# Power.net
KiCad netlist of a schematic drawn in Altium Designer
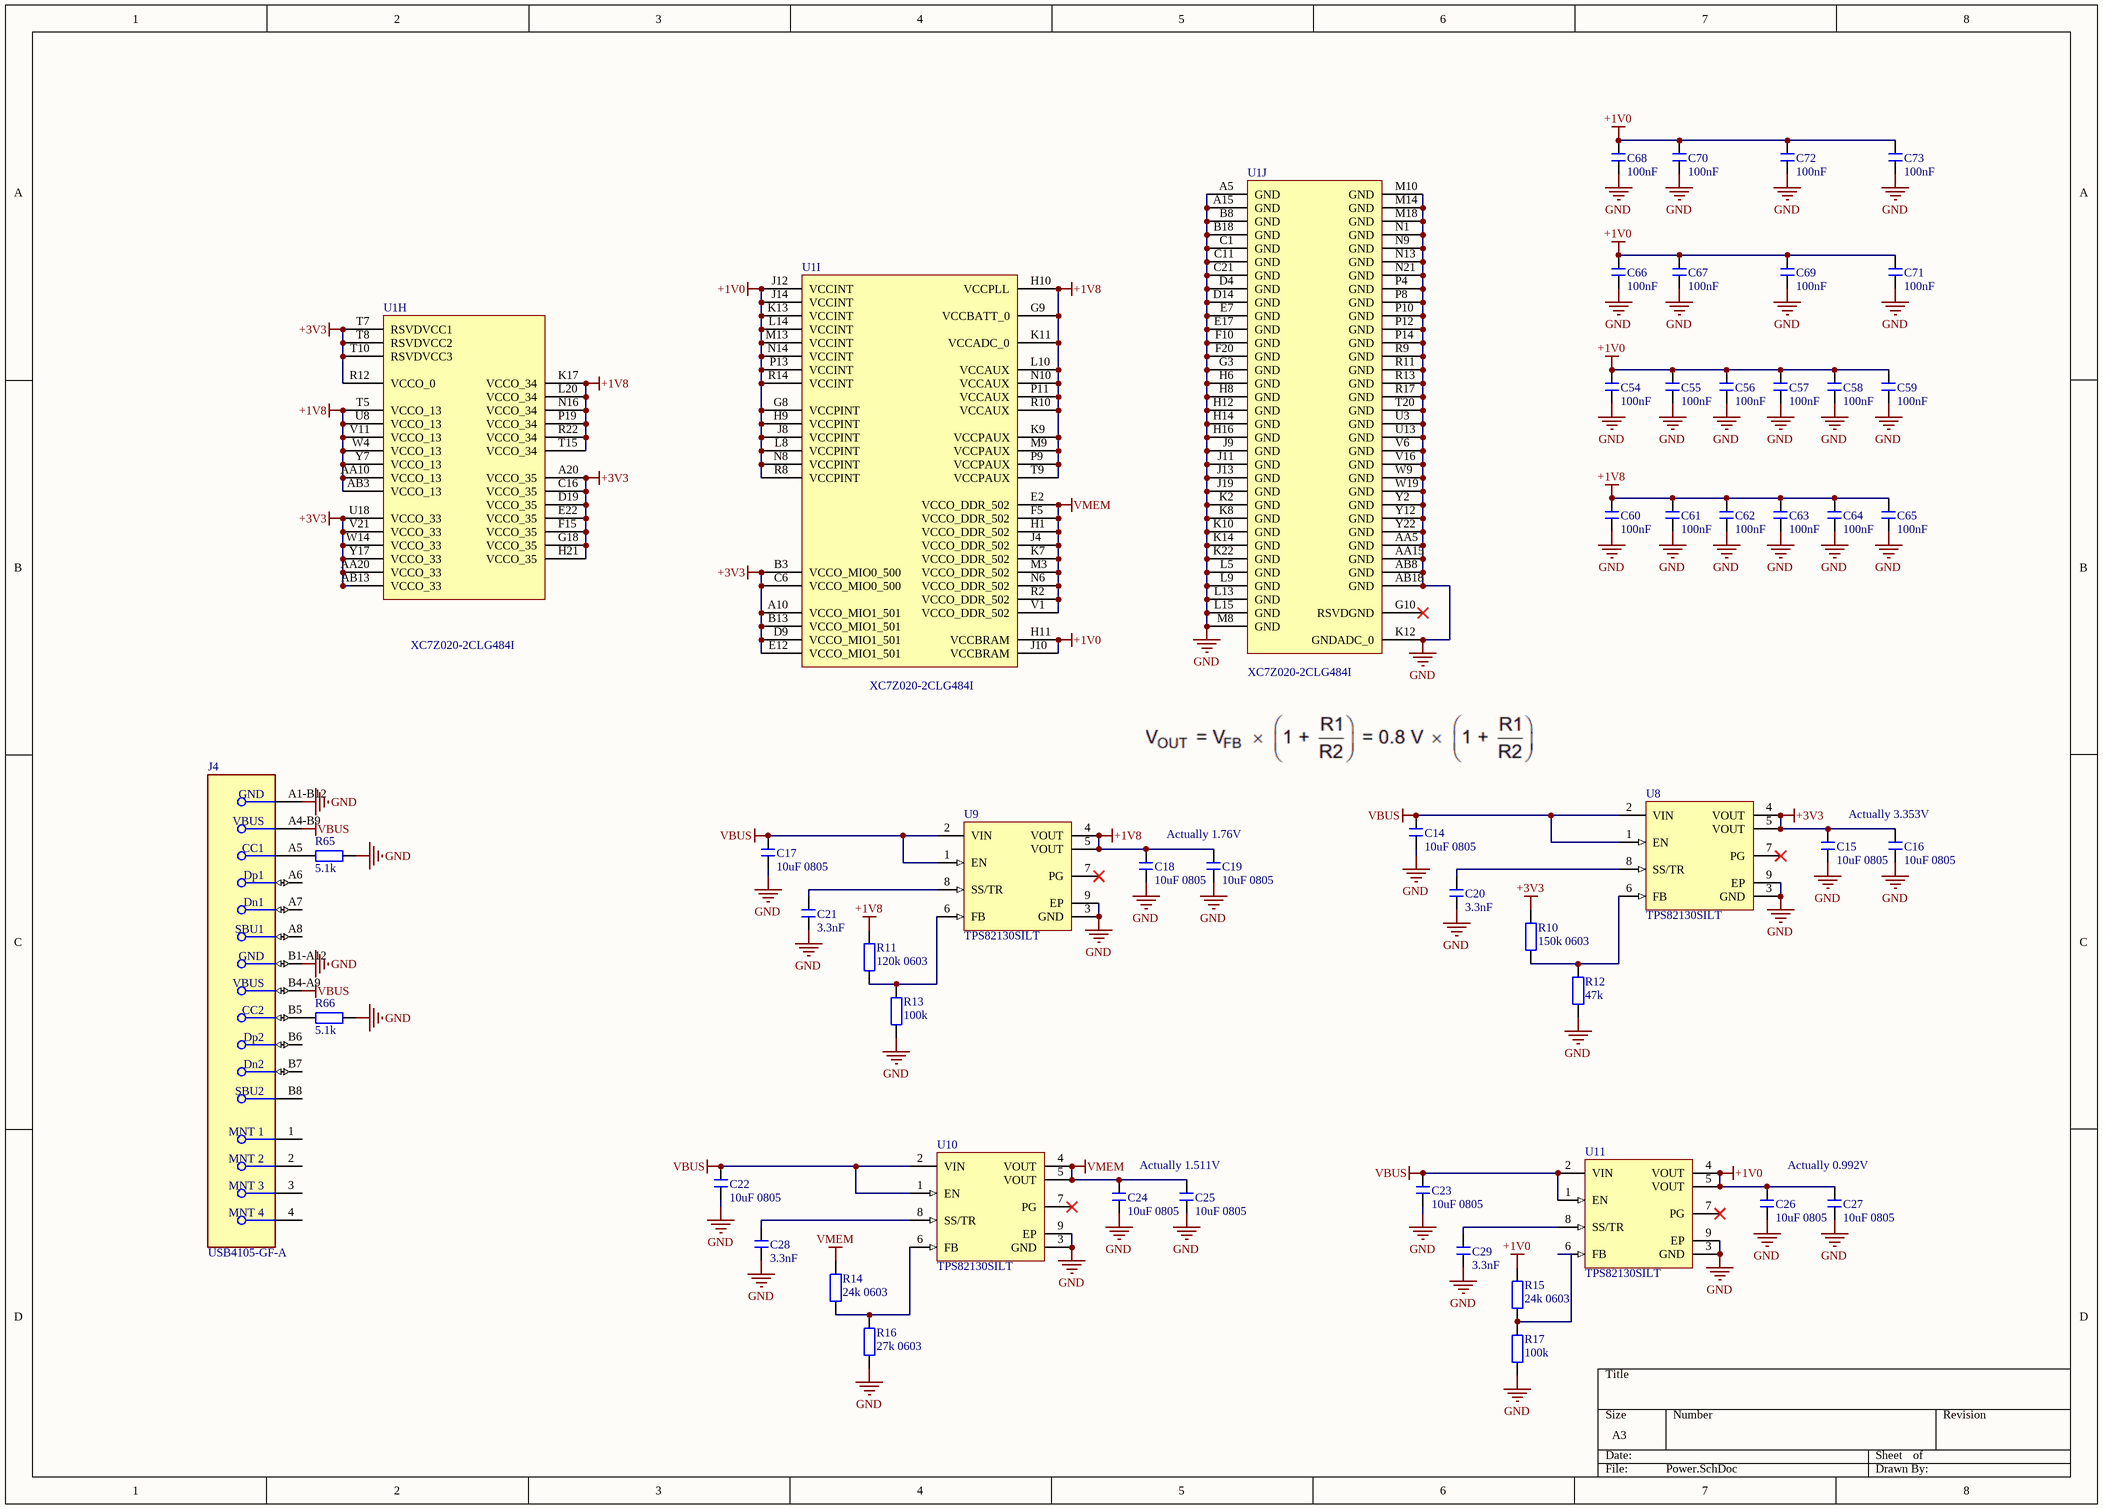
[diagram p0: Power.SchDoc]

(export (version "E")
  (design (tool "Eeschema 10.0.6"))
  (components
    (comp (ref "C14") (value "10uF 0805") (footprint "C0603") (libsource (lib "Passive") (part "C")))
    (comp (ref "C15") (value "10uF 0805") (footprint "C0603") (libsource (lib "Passive") (part "C")))
    (comp (ref "C16") (value "10uF 0805") (footprint "C0603") (libsource (lib "Passive") (part "C")))
    (comp (ref "C17") (value "10uF 0805") (footprint "C0603") (libsource (lib "Passive") (part "C")))
    (comp (ref "C18") (value "10uF 0805") (footprint "C0603") (libsource (lib "Passive") (part "C")))
    (comp (ref "C19") (value "10uF 0805") (footprint "C0603") (libsource (lib "Passive") (part "C")))
    (comp (ref "C20") (value "3.3nF") (footprint "C0402") (libsource (lib "Passive") (part "C")))
    (comp (ref "C21") (value "3.3nF") (footprint "C0402") (libsource (lib "Passive") (part "C")))
    (comp (ref "C22") (value "10uF 0805") (footprint "C0603") (libsource (lib "Passive") (part "C")))
    (comp (ref "C23") (value "10uF 0805") (footprint "C0603") (libsource (lib "Passive") (part "C")))
    (comp (ref "C24") (value "10uF 0805") (footprint "C0603") (libsource (lib "Passive") (part "C")))
    (comp (ref "C25") (value "10uF 0805") (footprint "C0603") (libsource (lib "Passive") (part "C")))
    (comp (ref "C26") (value "10uF 0805") (footprint "C0603") (libsource (lib "Passive") (part "C")))
    (comp (ref "C27") (value "10uF 0805") (footprint "C0603") (libsource (lib "Passive") (part "C")))
    (comp (ref "C28") (value "3.3nF") (footprint "C0402") (libsource (lib "Passive") (part "C")))
    (comp (ref "C29") (value "3.3nF") (footprint "C0402") (libsource (lib "Passive") (part "C")))
    (comp (ref "C54") (value "100nF") (footprint "C0402") (libsource (lib "Passive") (part "C")))
    (comp (ref "C55") (value "100nF") (footprint "C0402") (libsource (lib "Passive") (part "C")))
    (comp (ref "C56") (value "100nF") (footprint "C0402") (libsource (lib "Passive") (part "C")))
    (comp (ref "C57") (value "100nF") (footprint "C0402") (libsource (lib "Passive") (part "C")))
    (comp (ref "C58") (value "100nF") (footprint "C0402") (libsource (lib "Passive") (part "C")))
    (comp (ref "C59") (value "100nF") (footprint "C0402") (libsource (lib "Passive") (part "C")))
    (comp (ref "C60") (value "100nF") (footprint "C0402") (libsource (lib "Passive") (part "C")))
    (comp (ref "C61") (value "100nF") (footprint "C0402") (libsource (lib "Passive") (part "C")))
    (comp (ref "C62") (value "100nF") (footprint "C0402") (libsource (lib "Passive") (part "C")))
    (comp (ref "C63") (value "100nF") (footprint "C0402") (libsource (lib "Passive") (part "C")))
    (comp (ref "C64") (value "100nF") (footprint "C0402") (libsource (lib "Passive") (part "C")))
    (comp (ref "C65") (value "100nF") (footprint "C0402") (libsource (lib "Passive") (part "C")))
    (comp (ref "C66") (value "100nF") (footprint "C0402") (libsource (lib "Passive") (part "C")))
    (comp (ref "C67") (value "100nF") (footprint "C0402") (libsource (lib "Passive") (part "C")))
    (comp (ref "C68") (value "100nF") (footprint "C0402") (libsource (lib "Passive") (part "C")))
    (comp (ref "C69") (value "100nF") (footprint "C0402") (libsource (lib "Passive") (part "C")))
    (comp (ref "C70") (value "100nF") (footprint "C0402") (libsource (lib "Passive") (part "C")))
    (comp (ref "C71") (value "100nF") (footprint "C0402") (libsource (lib "Passive") (part "C")))
    (comp (ref "C72") (value "100nF") (footprint "C0402") (libsource (lib "Passive") (part "C")))
    (comp (ref "C73") (value "100nF") (footprint "C0402") (libsource (lib "Passive") (part "C")))
    (comp (ref "J4")
      (value "USB4105-GF-A")
      (footprint "FP-USB4105-GF-A-MFG")
      (description "CONN RCPT USB2.0 TYPEC 5A")
      (fields
        (field (name "MANUFACTURER") "GCT")
        (field (name "OCTOPART") "https://octopart.com/usb4105-gf-a-gct-106627878")
      )
      (libsource (lib "Altium Content Vault") (part "e7c17a616881a82b79941196b4bec10"))
    )
    (comp (ref "R10") (value "150k 0603") (footprint "R0603") (libsource (lib "Passive") (part "R")))
    (comp (ref "R11") (value "120k 0603") (footprint "R0603") (libsource (lib "Passive") (part "R")))
    (comp (ref "R12") (value "47k") (footprint "R0402") (libsource (lib "Passive") (part "R")))
    (comp (ref "R13") (value "100k") (footprint "R0402") (libsource (lib "Passive") (part "R")))
    (comp (ref "R14") (value "24k 0603") (footprint "R0603") (libsource (lib "Passive") (part "R")))
    (comp (ref "R15") (value "24k 0603") (footprint "R0603") (libsource (lib "Passive") (part "R")))
    (comp (ref "R16") (value "27k 0603") (footprint "R0603") (libsource (lib "Passive") (part "R")))
    (comp (ref "R17") (value "100k") (footprint "R0402") (libsource (lib "Passive") (part "R")))
    (comp (ref "R65") (value "5.1k") (footprint "R0402") (libsource (lib "Passive") (part "R")))
    (comp (ref "R66") (value "5.1k") (footprint "R0402") (libsource (lib "Passive") (part "R")))
    (comp (ref "U1")
      (value "XC7Z020-2CLG484I")
      (footprint "CLG484")
      (fields (field (name "GENERIC PART NUMBER") "XC7Z020"))
      (libsource (lib "Altium Content Vault") (part "XNLX-XC7Z020-CLG484"))
    )
    (comp (ref "U8")
      (value "TPS82130SILT")
      (footprint "SIL0008D_V")
      (fields (field (name "MANUFACTURER") "Texas Instruments"))
      (libsource (lib "Altium Content Vault") (part "TI-TPS82130-SIL-8"))
    )
    (comp (ref "U9")
      (value "TPS82130SILT")
      (footprint "SIL0008D_V")
      (fields (field (name "MANUFACTURER") "Texas Instruments"))
      (libsource (lib "Altium Content Vault") (part "TI-TPS82130-SIL-8"))
    )
    (comp (ref "U10")
      (value "TPS82130SILT")
      (footprint "SIL0008D_V")
      (fields (field (name "MANUFACTURER") "Texas Instruments"))
      (libsource (lib "Altium Content Vault") (part "TI-TPS82130-SIL-8"))
    )
    (comp (ref "U11")
      (value "TPS82130SILT")
      (footprint "SIL0008D_V")
      (fields (field (name "MANUFACTURER") "Texas Instruments"))
      (libsource (lib "Altium Content Vault") (part "TI-TPS82130-SIL-8"))
    )
  )
  (nets
    (net (code "1") (name "+1V0") (class "Default")
      (node (ref "C26") (pin "2") (pinfunction "2_2") (pintype "passive"))
      (node (ref "C27") (pin "2") (pinfunction "2_2") (pintype "passive"))
      (node (ref "C54") (pin "2") (pinfunction "2_2") (pintype "passive"))
      (node (ref "C55") (pin "2") (pinfunction "2_2") (pintype "passive"))
      (node (ref "C56") (pin "2") (pinfunction "2_2") (pintype "passive"))
      (node (ref "C57") (pin "2") (pinfunction "2_2") (pintype "passive"))
      (node (ref "C58") (pin "2") (pinfunction "2_2") (pintype "passive"))
      (node (ref "C59") (pin "2") (pinfunction "2_2") (pintype "passive"))
      (node (ref "C66") (pin "2") (pinfunction "2_2") (pintype "passive"))
      (node (ref "C67") (pin "2") (pinfunction "2_2") (pintype "passive"))
      (node (ref "C68") (pin "2") (pinfunction "2_2") (pintype "passive"))
      (node (ref "C69") (pin "2") (pinfunction "2_2") (pintype "passive"))
      (node (ref "C70") (pin "2") (pinfunction "2_2") (pintype "passive"))
      (node (ref "C71") (pin "2") (pinfunction "2_2") (pintype "passive"))
      (node (ref "C72") (pin "2") (pinfunction "2_2") (pintype "passive"))
      (node (ref "C73") (pin "2") (pinfunction "2_2") (pintype "passive"))
      (node (ref "R15") (pin "1") (pinfunction "1_1") (pintype "passive"))
      (node (ref "U1") (pin "G8") (pinfunction "VCCPINT_G8") (pintype "power_in"))
      (node (ref "U1") (pin "H11") (pinfunction "VCCBRAM_H11") (pintype "power_in"))
      (node (ref "U1") (pin "H9") (pinfunction "VCCPINT_H9") (pintype "power_in"))
      (node (ref "U1") (pin "J10") (pinfunction "VCCBRAM_J10") (pintype "power_in"))
      (node (ref "U1") (pin "J12") (pinfunction "VCCINT_J12") (pintype "power_in"))
      (node (ref "U1") (pin "J14") (pinfunction "VCCINT_J14") (pintype "power_in"))
      (node (ref "U1") (pin "J8") (pinfunction "VCCPINT_J8") (pintype "power_in"))
      (node (ref "U1") (pin "K13") (pinfunction "VCCINT_K13") (pintype "power_in"))
      (node (ref "U1") (pin "L14") (pinfunction "VCCINT_L14") (pintype "power_in"))
      (node (ref "U1") (pin "L8") (pinfunction "VCCPINT_L8") (pintype "power_in"))
      (node (ref "U1") (pin "M13") (pinfunction "VCCINT_M13") (pintype "power_in"))
      (node (ref "U1") (pin "N14") (pinfunction "VCCINT_N14") (pintype "power_in"))
      (node (ref "U1") (pin "N8") (pinfunction "VCCPINT_N8") (pintype "power_in"))
      (node (ref "U1") (pin "P13") (pinfunction "VCCINT_P13") (pintype "power_in"))
      (node (ref "U1") (pin "R14") (pinfunction "VCCINT_R14") (pintype "power_in"))
      (node (ref "U1") (pin "R8") (pinfunction "VCCPINT_R8") (pintype "power_in"))
      (node (ref "U11") (pin "4") (pinfunction "VOUT_4") (pintype "power_in"))
      (node (ref "U11") (pin "5") (pinfunction "VOUT_5") (pintype "power_in"))
    )
    (net (code "2") (name "+1V8") (class "Default")
      (node (ref "C18") (pin "2") (pinfunction "2_2") (pintype "passive"))
      (node (ref "C19") (pin "2") (pinfunction "2_2") (pintype "passive"))
      (node (ref "C60") (pin "2") (pinfunction "2_2") (pintype "passive"))
      (node (ref "C61") (pin "2") (pinfunction "2_2") (pintype "passive"))
      (node (ref "C62") (pin "2") (pinfunction "2_2") (pintype "passive"))
      (node (ref "C63") (pin "2") (pinfunction "2_2") (pintype "passive"))
      (node (ref "C64") (pin "2") (pinfunction "2_2") (pintype "passive"))
      (node (ref "C65") (pin "2") (pinfunction "2_2") (pintype "passive"))
      (node (ref "R11") (pin "1") (pinfunction "1_1") (pintype "passive"))
      (node (ref "U1") (pin "AA10") (pinfunction "VCCO_13_AA10") (pintype "power_in"))
      (node (ref "U1") (pin "AB3") (pinfunction "VCCO_13_AB3") (pintype "power_in"))
      (node (ref "U1") (pin "G9") (pinfunction "VCCBATT_0_G9") (pintype "power_in"))
      (node (ref "U1") (pin "H10") (pinfunction "VCCPLL_H10") (pintype "power_in"))
      (node (ref "U1") (pin "K11") (pinfunction "VCCADC_0_K11") (pintype "power_in"))
      (node (ref "U1") (pin "K17") (pinfunction "VCCO_34_K17") (pintype "power_in"))
      (node (ref "U1") (pin "K9") (pinfunction "VCCPAUX_K9") (pintype "power_in"))
      (node (ref "U1") (pin "L10") (pinfunction "VCCAUX_L10") (pintype "power_in"))
      (node (ref "U1") (pin "L20") (pinfunction "VCCO_34_L20") (pintype "power_in"))
      (node (ref "U1") (pin "M9") (pinfunction "VCCPAUX_M9") (pintype "power_in"))
      (node (ref "U1") (pin "N10") (pinfunction "VCCAUX_N10") (pintype "power_in"))
      (node (ref "U1") (pin "N16") (pinfunction "VCCO_34_N16") (pintype "power_in"))
      (node (ref "U1") (pin "P11") (pinfunction "VCCAUX_P11") (pintype "power_in"))
      (node (ref "U1") (pin "P19") (pinfunction "VCCO_34_P19") (pintype "power_in"))
      (node (ref "U1") (pin "P9") (pinfunction "VCCPAUX_P9") (pintype "power_in"))
      (node (ref "U1") (pin "R10") (pinfunction "VCCAUX_R10") (pintype "power_in"))
      (node (ref "U1") (pin "R22") (pinfunction "VCCO_34_R22") (pintype "power_in"))
      (node (ref "U1") (pin "T15") (pinfunction "VCCO_34_T15") (pintype "power_in"))
      (node (ref "U1") (pin "T5") (pinfunction "VCCO_13_T5") (pintype "power_in"))
      (node (ref "U1") (pin "T9") (pinfunction "VCCPAUX_T9") (pintype "power_in"))
      (node (ref "U1") (pin "U8") (pinfunction "VCCO_13_U8") (pintype "power_in"))
      (node (ref "U1") (pin "V11") (pinfunction "VCCO_13_V11") (pintype "power_in"))
      (node (ref "U1") (pin "W4") (pinfunction "VCCO_13_W4") (pintype "power_in"))
      (node (ref "U1") (pin "Y7") (pinfunction "VCCO_13_Y7") (pintype "power_in"))
      (node (ref "U9") (pin "4") (pinfunction "VOUT_4") (pintype "power_in"))
      (node (ref "U9") (pin "5") (pinfunction "VOUT_5") (pintype "power_in"))
    )
    (net (code "3") (name "+3V3") (class "Default")
      (node (ref "C15") (pin "2") (pinfunction "2_2") (pintype "passive"))
      (node (ref "C16") (pin "2") (pinfunction "2_2") (pintype "passive"))
      (node (ref "R10") (pin "1") (pinfunction "1_1") (pintype "passive"))
      (node (ref "U1") (pin "A10") (pinfunction "VCCO_MIO1_501_A10") (pintype "power_in"))
      (node (ref "U1") (pin "A20") (pinfunction "VCCO_35_A20") (pintype "power_in"))
      (node (ref "U1") (pin "AA20") (pinfunction "VCCO_33_AA20") (pintype "power_in"))
      (node (ref "U1") (pin "AB13") (pinfunction "VCCO_33_AB13") (pintype "power_in"))
      (node (ref "U1") (pin "B13") (pinfunction "VCCO_MIO1_501_B13") (pintype "power_in"))
      (node (ref "U1") (pin "B3") (pinfunction "VCCO_MIO0_500_B3") (pintype "power_in"))
      (node (ref "U1") (pin "C16") (pinfunction "VCCO_35_C16") (pintype "power_in"))
      (node (ref "U1") (pin "C6") (pinfunction "VCCO_MIO0_500_C6") (pintype "power_in"))
      (node (ref "U1") (pin "D19") (pinfunction "VCCO_35_D19") (pintype "power_in"))
      (node (ref "U1") (pin "D9") (pinfunction "VCCO_MIO1_501_D9") (pintype "power_in"))
      (node (ref "U1") (pin "E12") (pinfunction "VCCO_MIO1_501_E12") (pintype "power_in"))
      (node (ref "U1") (pin "E22") (pinfunction "VCCO_35_E22") (pintype "power_in"))
      (node (ref "U1") (pin "F15") (pinfunction "VCCO_35_F15") (pintype "power_in"))
      (node (ref "U1") (pin "G18") (pinfunction "VCCO_35_G18") (pintype "power_in"))
      (node (ref "U1") (pin "H21") (pinfunction "VCCO_35_H21") (pintype "power_in"))
      (node (ref "U1") (pin "R12") (pinfunction "VCCO_0_R12") (pintype "power_in"))
      (node (ref "U1") (pin "T10") (pinfunction "RSVDVCC3_T10") (pintype "power_in"))
      (node (ref "U1") (pin "T7") (pinfunction "RSVDVCC1_T7") (pintype "power_in"))
      (node (ref "U1") (pin "T8") (pinfunction "RSVDVCC2_T8") (pintype "power_in"))
      (node (ref "U1") (pin "U18") (pinfunction "VCCO_33_U18") (pintype "power_in"))
      (node (ref "U1") (pin "V21") (pinfunction "VCCO_33_V21") (pintype "power_in"))
      (node (ref "U1") (pin "W14") (pinfunction "VCCO_33_W14") (pintype "power_in"))
      (node (ref "U1") (pin "Y17") (pinfunction "VCCO_33_Y17") (pintype "power_in"))
      (node (ref "U8") (pin "4") (pinfunction "VOUT_4") (pintype "power_in"))
      (node (ref "U8") (pin "5") (pinfunction "VOUT_5") (pintype "power_in"))
    )
    (net (code "4") (name "GND") (class "Default")
      (node (ref "C14") (pin "1") (pinfunction "1_1") (pintype "passive"))
      (node (ref "C15") (pin "1") (pinfunction "1_1") (pintype "passive"))
      (node (ref "C16") (pin "1") (pinfunction "1_1") (pintype "passive"))
      (node (ref "C17") (pin "1") (pinfunction "1_1") (pintype "passive"))
      (node (ref "C18") (pin "1") (pinfunction "1_1") (pintype "passive"))
      (node (ref "C19") (pin "1") (pinfunction "1_1") (pintype "passive"))
      (node (ref "C20") (pin "1") (pinfunction "1_1") (pintype "passive"))
      (node (ref "C21") (pin "1") (pinfunction "1_1") (pintype "passive"))
      (node (ref "C22") (pin "1") (pinfunction "1_1") (pintype "passive"))
      (node (ref "C23") (pin "1") (pinfunction "1_1") (pintype "passive"))
      (node (ref "C24") (pin "1") (pinfunction "1_1") (pintype "passive"))
      (node (ref "C25") (pin "1") (pinfunction "1_1") (pintype "passive"))
      (node (ref "C26") (pin "1") (pinfunction "1_1") (pintype "passive"))
      (node (ref "C27") (pin "1") (pinfunction "1_1") (pintype "passive"))
      (node (ref "C28") (pin "1") (pinfunction "1_1") (pintype "passive"))
      (node (ref "C29") (pin "1") (pinfunction "1_1") (pintype "passive"))
      (node (ref "C54") (pin "1") (pinfunction "1_1") (pintype "passive"))
      (node (ref "C55") (pin "1") (pinfunction "1_1") (pintype "passive"))
      (node (ref "C56") (pin "1") (pinfunction "1_1") (pintype "passive"))
      (node (ref "C57") (pin "1") (pinfunction "1_1") (pintype "passive"))
      (node (ref "C58") (pin "1") (pinfunction "1_1") (pintype "passive"))
      (node (ref "C59") (pin "1") (pinfunction "1_1") (pintype "passive"))
      (node (ref "C60") (pin "1") (pinfunction "1_1") (pintype "passive"))
      (node (ref "C61") (pin "1") (pinfunction "1_1") (pintype "passive"))
      (node (ref "C62") (pin "1") (pinfunction "1_1") (pintype "passive"))
      (node (ref "C63") (pin "1") (pinfunction "1_1") (pintype "passive"))
      (node (ref "C64") (pin "1") (pinfunction "1_1") (pintype "passive"))
      (node (ref "C65") (pin "1") (pinfunction "1_1") (pintype "passive"))
      (node (ref "C66") (pin "1") (pinfunction "1_1") (pintype "passive"))
      (node (ref "C67") (pin "1") (pinfunction "1_1") (pintype "passive"))
      (node (ref "C68") (pin "1") (pinfunction "1_1") (pintype "passive"))
      (node (ref "C69") (pin "1") (pinfunction "1_1") (pintype "passive"))
      (node (ref "C70") (pin "1") (pinfunction "1_1") (pintype "passive"))
      (node (ref "C71") (pin "1") (pinfunction "1_1") (pintype "passive"))
      (node (ref "C72") (pin "1") (pinfunction "1_1") (pintype "passive"))
      (node (ref "C73") (pin "1") (pinfunction "1_1") (pintype "passive"))
      (node (ref "J4") (pin "A1-B12") (pinfunction "GND_A1-B12") (pintype "power_in"))
      (node (ref "J4") (pin "B1-A12") (pinfunction "GND_B1-A12") (pintype "bidirectional"))
      (node (ref "R12") (pin "2") (pinfunction "2_2") (pintype "passive"))
      (node (ref "R13") (pin "2") (pinfunction "2_2") (pintype "passive"))
      (node (ref "R16") (pin "2") (pinfunction "2_2") (pintype "passive"))
      (node (ref "R17") (pin "2") (pinfunction "2_2") (pintype "passive"))
      (node (ref "R65") (pin "2") (pinfunction "2_2") (pintype "passive"))
      (node (ref "R66") (pin "2") (pinfunction "2_2") (pintype "passive"))
      (node (ref "U1") (pin "A15") (pinfunction "GND_A15") (pintype "power_in"))
      (node (ref "U1") (pin "A5") (pinfunction "GND_A5") (pintype "power_in"))
      (node (ref "U1") (pin "AA15") (pinfunction "GND_AA15") (pintype "power_in"))
      (node (ref "U1") (pin "AA5") (pinfunction "GND_AA5") (pintype "power_in"))
      (node (ref "U1") (pin "AB18") (pinfunction "GND_AB18") (pintype "power_in"))
      (node (ref "U1") (pin "AB8") (pinfunction "GND_AB8") (pintype "power_in"))
      (node (ref "U1") (pin "B18") (pinfunction "GND_B18") (pintype "power_in"))
      (node (ref "U1") (pin "B8") (pinfunction "GND_B8") (pintype "power_in"))
      (node (ref "U1") (pin "C1") (pinfunction "GND_C1") (pintype "power_in"))
      (node (ref "U1") (pin "C11") (pinfunction "GND_C11") (pintype "power_in"))
      (node (ref "U1") (pin "C21") (pinfunction "GND_C21") (pintype "power_in"))
      (node (ref "U1") (pin "D14") (pinfunction "GND_D14") (pintype "power_in"))
      (node (ref "U1") (pin "D4") (pinfunction "GND_D4") (pintype "power_in"))
      (node (ref "U1") (pin "E17") (pinfunction "GND_E17") (pintype "power_in"))
      (node (ref "U1") (pin "E7") (pinfunction "GND_E7") (pintype "power_in"))
      (node (ref "U1") (pin "F10") (pinfunction "GND_F10") (pintype "power_in"))
      (node (ref "U1") (pin "F20") (pinfunction "GND_F20") (pintype "power_in"))
      (node (ref "U1") (pin "G3") (pinfunction "GND_G3") (pintype "power_in"))
      (node (ref "U1") (pin "H12") (pinfunction "GND_H12") (pintype "power_in"))
      (node (ref "U1") (pin "H14") (pinfunction "GND_H14") (pintype "power_in"))
      (node (ref "U1") (pin "H16") (pinfunction "GND_H16") (pintype "power_in"))
      (node (ref "U1") (pin "H6") (pinfunction "GND_H6") (pintype "power_in"))
      (node (ref "U1") (pin "H8") (pinfunction "GND_H8") (pintype "power_in"))
      (node (ref "U1") (pin "J11") (pinfunction "GND_J11") (pintype "power_in"))
      (node (ref "U1") (pin "J13") (pinfunction "GND_J13") (pintype "power_in"))
      (node (ref "U1") (pin "J19") (pinfunction "GND_J19") (pintype "power_in"))
      (node (ref "U1") (pin "J9") (pinfunction "GND_J9") (pintype "power_in"))
      (node (ref "U1") (pin "K10") (pinfunction "GND_K10") (pintype "power_in"))
      (node (ref "U1") (pin "K12") (pinfunction "GNDADC_0_K12") (pintype "power_in"))
      (node (ref "U1") (pin "K14") (pinfunction "GND_K14") (pintype "power_in"))
      (node (ref "U1") (pin "K2") (pinfunction "GND_K2") (pintype "power_in"))
      (node (ref "U1") (pin "K22") (pinfunction "GND_K22") (pintype "power_in"))
      (node (ref "U1") (pin "K8") (pinfunction "GND_K8") (pintype "power_in"))
      (node (ref "U1") (pin "L13") (pinfunction "GND_L13") (pintype "power_in"))
      (node (ref "U1") (pin "L15") (pinfunction "GND_L15") (pintype "power_in"))
      (node (ref "U1") (pin "L5") (pinfunction "GND_L5") (pintype "power_in"))
      (node (ref "U1") (pin "L9") (pinfunction "GND_L9") (pintype "power_in"))
      (node (ref "U1") (pin "M10") (pinfunction "GND_M10") (pintype "power_in"))
      (node (ref "U1") (pin "M14") (pinfunction "GND_M14") (pintype "power_in"))
      (node (ref "U1") (pin "M18") (pinfunction "GND_M18") (pintype "power_in"))
      (node (ref "U1") (pin "M8") (pinfunction "GND_M8") (pintype "power_in"))
      (node (ref "U1") (pin "N1") (pinfunction "GND_N1") (pintype "power_in"))
      (node (ref "U1") (pin "N13") (pinfunction "GND_N13") (pintype "power_in"))
      (node (ref "U1") (pin "N21") (pinfunction "GND_N21") (pintype "power_in"))
      (node (ref "U1") (pin "N9") (pinfunction "GND_N9") (pintype "power_in"))
      (node (ref "U1") (pin "P10") (pinfunction "GND_P10") (pintype "power_in"))
      (node (ref "U1") (pin "P12") (pinfunction "GND_P12") (pintype "power_in"))
      (node (ref "U1") (pin "P14") (pinfunction "GND_P14") (pintype "power_in"))
      (node (ref "U1") (pin "P4") (pinfunction "GND_P4") (pintype "power_in"))
      (node (ref "U1") (pin "P8") (pinfunction "GND_P8") (pintype "power_in"))
      (node (ref "U1") (pin "R11") (pinfunction "GND_R11") (pintype "power_in"))
      (node (ref "U1") (pin "R13") (pinfunction "GND_R13") (pintype "power_in"))
      (node (ref "U1") (pin "R17") (pinfunction "GND_R17") (pintype "power_in"))
      (node (ref "U1") (pin "R9") (pinfunction "GND_R9") (pintype "power_in"))
      (node (ref "U1") (pin "T20") (pinfunction "GND_T20") (pintype "power_in"))
      (node (ref "U1") (pin "U13") (pinfunction "GND_U13") (pintype "power_in"))
      (node (ref "U1") (pin "U3") (pinfunction "GND_U3") (pintype "power_in"))
      (node (ref "U1") (pin "V16") (pinfunction "GND_V16") (pintype "power_in"))
      (node (ref "U1") (pin "V6") (pinfunction "GND_V6") (pintype "power_in"))
      (node (ref "U1") (pin "W19") (pinfunction "GND_W19") (pintype "power_in"))
      (node (ref "U1") (pin "W9") (pinfunction "GND_W9") (pintype "power_in"))
      (node (ref "U1") (pin "Y12") (pinfunction "GND_Y12") (pintype "power_in"))
      (node (ref "U1") (pin "Y2") (pinfunction "GND_Y2") (pintype "power_in"))
      (node (ref "U1") (pin "Y22") (pinfunction "GND_Y22") (pintype "power_in"))
      (node (ref "U10") (pin "3") (pinfunction "GND_3") (pintype "power_in"))
      (node (ref "U10") (pin "9") (pinfunction "EP_9") (pintype "power_in"))
      (node (ref "U11") (pin "3") (pinfunction "GND_3") (pintype "power_in"))
      (node (ref "U11") (pin "9") (pinfunction "EP_9") (pintype "power_in"))
      (node (ref "U8") (pin "3") (pinfunction "GND_3") (pintype "power_in"))
      (node (ref "U8") (pin "9") (pinfunction "EP_9") (pintype "power_in"))
      (node (ref "U9") (pin "3") (pinfunction "GND_3") (pintype "power_in"))
      (node (ref "U9") (pin "9") (pinfunction "EP_9") (pintype "power_in"))
    )
    (net (code "5") (name "Net-(J4-CC1)") (class "Default")
      (node (ref "J4") (pin "A5") (pinfunction "CC1_A5") (pintype "power_in"))
      (node (ref "R65") (pin "1") (pinfunction "1_1") (pintype "passive"))
    )
    (net (code "6") (name "Net-(J4-CC2)") (class "Default")
      (node (ref "J4") (pin "B5") (pinfunction "CC2_B5") (pintype "bidirectional"))
      (node (ref "R66") (pin "1") (pinfunction "1_1") (pintype "passive"))
    )
    (net (code "7") (name "Net-(U8-FB)") (class "Default")
      (node (ref "R10") (pin "2") (pinfunction "2_2") (pintype "passive"))
      (node (ref "R12") (pin "1") (pinfunction "1_1") (pintype "passive"))
      (node (ref "U8") (pin "6") (pinfunction "FB_6") (pintype "input"))
    )
    (net (code "8") (name "Net-(U8-SS{slash}TR)") (class "Default")
      (node (ref "C20") (pin "2") (pinfunction "2_2") (pintype "passive"))
      (node (ref "U8") (pin "8") (pinfunction "SS/TR_8") (pintype "input"))
    )
    (net (code "9") (name "Net-(U9-FB)") (class "Default")
      (node (ref "R11") (pin "2") (pinfunction "2_2") (pintype "passive"))
      (node (ref "R13") (pin "1") (pinfunction "1_1") (pintype "passive"))
      (node (ref "U9") (pin "6") (pinfunction "FB_6") (pintype "input"))
    )
    (net (code "10") (name "Net-(U9-SS{slash}TR)") (class "Default")
      (node (ref "C21") (pin "2") (pinfunction "2_2") (pintype "passive"))
      (node (ref "U9") (pin "8") (pinfunction "SS/TR_8") (pintype "input"))
    )
    (net (code "11") (name "Net-(U10-FB)") (class "Default")
      (node (ref "R14") (pin "2") (pinfunction "2_2") (pintype "passive"))
      (node (ref "R16") (pin "1") (pinfunction "1_1") (pintype "passive"))
      (node (ref "U10") (pin "6") (pinfunction "FB_6") (pintype "input"))
    )
    (net (code "12") (name "Net-(U10-SS{slash}TR)") (class "Default")
      (node (ref "C28") (pin "2") (pinfunction "2_2") (pintype "passive"))
      (node (ref "U10") (pin "8") (pinfunction "SS/TR_8") (pintype "input"))
    )
    (net (code "13") (name "Net-(U11-FB)") (class "Default")
      (node (ref "R15") (pin "2") (pinfunction "2_2") (pintype "passive"))
      (node (ref "R17") (pin "1") (pinfunction "1_1") (pintype "passive"))
      (node (ref "U11") (pin "6") (pinfunction "FB_6") (pintype "input"))
    )
    (net (code "14") (name "Net-(U11-SS{slash}TR)") (class "Default")
      (node (ref "C29") (pin "2") (pinfunction "2_2") (pintype "passive"))
      (node (ref "U11") (pin "8") (pinfunction "SS/TR_8") (pintype "input"))
    )
    (net (code "15") (name "VBUS") (class "Default")
      (node (ref "C14") (pin "2") (pinfunction "2_2") (pintype "passive"))
      (node (ref "C17") (pin "2") (pinfunction "2_2") (pintype "passive"))
      (node (ref "C22") (pin "2") (pinfunction "2_2") (pintype "passive"))
      (node (ref "C23") (pin "2") (pinfunction "2_2") (pintype "passive"))
      (node (ref "J4") (pin "A4-B9") (pinfunction "VBUS_A4-B9") (pintype "power_in"))
      (node (ref "J4") (pin "B4-A9") (pinfunction "VBUS_B4-A9") (pintype "bidirectional"))
      (node (ref "U10") (pin "1") (pinfunction "EN_1") (pintype "input"))
      (node (ref "U10") (pin "2") (pinfunction "VIN_2") (pintype "power_in"))
      (node (ref "U11") (pin "1") (pinfunction "EN_1") (pintype "input"))
      (node (ref "U11") (pin "2") (pinfunction "VIN_2") (pintype "power_in"))
      (node (ref "U8") (pin "1") (pinfunction "EN_1") (pintype "input"))
      (node (ref "U8") (pin "2") (pinfunction "VIN_2") (pintype "power_in"))
      (node (ref "U9") (pin "1") (pinfunction "EN_1") (pintype "input"))
      (node (ref "U9") (pin "2") (pinfunction "VIN_2") (pintype "power_in"))
    )
    (net (code "16") (name "VMEM") (class "Default")
      (node (ref "C24") (pin "2") (pinfunction "2_2") (pintype "passive"))
      (node (ref "C25") (pin "2") (pinfunction "2_2") (pintype "passive"))
      (node (ref "R14") (pin "1") (pinfunction "1_1") (pintype "passive"))
      (node (ref "U1") (pin "E2") (pinfunction "VCCO_DDR_502_E2") (pintype "power_in"))
      (node (ref "U1") (pin "F5") (pinfunction "VCCO_DDR_502_F5") (pintype "power_in"))
      (node (ref "U1") (pin "H1") (pinfunction "VCCO_DDR_502_H1") (pintype "power_in"))
      (node (ref "U1") (pin "J4") (pinfunction "VCCO_DDR_502_J4") (pintype "power_in"))
      (node (ref "U1") (pin "K7") (pinfunction "VCCO_DDR_502_K7") (pintype "power_in"))
      (node (ref "U1") (pin "M3") (pinfunction "VCCO_DDR_502_M3") (pintype "power_in"))
      (node (ref "U1") (pin "N6") (pinfunction "VCCO_DDR_502_N6") (pintype "power_in"))
      (node (ref "U1") (pin "R2") (pinfunction "VCCO_DDR_502_R2") (pintype "power_in"))
      (node (ref "U1") (pin "V1") (pinfunction "VCCO_DDR_502_V1") (pintype "power_in"))
      (node (ref "U10") (pin "4") (pinfunction "VOUT_4") (pintype "power_in"))
      (node (ref "U10") (pin "5") (pinfunction "VOUT_5") (pintype "power_in"))
    )
    (net (code "17") (name "unconnected-(J4-Dn1-PadA7)") (class "Default")
      (node (ref "J4") (pin "A7") (pinfunction "Dn1_A7") (pintype "bidirectional"))
    )
    (net (code "18") (name "unconnected-(J4-Dn2-PadB7)") (class "Default")
      (node (ref "J4") (pin "B7") (pinfunction "Dn2_B7") (pintype "bidirectional"))
    )
    (net (code "19") (name "unconnected-(J4-Dp1-PadA6)") (class "Default")
      (node (ref "J4") (pin "A6") (pinfunction "Dp1_A6") (pintype "bidirectional"))
    )
    (net (code "20") (name "unconnected-(J4-Dp2-PadB6)") (class "Default")
      (node (ref "J4") (pin "B6") (pinfunction "Dp2_B6") (pintype "bidirectional"))
    )
    (net (code "21") (name "unconnected-(J4-MNT_1-Pad1)") (class "Default")
      (node (ref "J4") (pin "1") (pinfunction "MNT_1_1") (pintype "power_in"))
    )
    (net (code "22") (name "unconnected-(J4-MNT_2-Pad2)") (class "Default")
      (node (ref "J4") (pin "2") (pinfunction "MNT_2_2") (pintype "power_in"))
    )
    (net (code "23") (name "unconnected-(J4-MNT_3-Pad3)") (class "Default")
      (node (ref "J4") (pin "3") (pinfunction "MNT_3_3") (pintype "power_in"))
    )
    (net (code "24") (name "unconnected-(J4-MNT_4-Pad4)") (class "Default")
      (node (ref "J4") (pin "4") (pinfunction "MNT_4_4") (pintype "power_in"))
    )
    (net (code "25") (name "unconnected-(J4-SBU1-PadA8)") (class "Default")
      (node (ref "J4") (pin "A8") (pinfunction "SBU1_A8") (pintype "bidirectional"))
    )
    (net (code "26") (name "unconnected-(J4-SBU2-PadB8)") (class "Default")
      (node (ref "J4") (pin "B8") (pinfunction "SBU2_B8") (pintype "power_in"))
    )
    (net (code "27") (name "unconnected-(U1J-RSVDGND-PadG10)") (class "Default")
      (node (ref "U1") (pin "G10") (pinfunction "RSVDGND_G10") (pintype "power_in+no_connect"))
    )
    (net (code "28") (name "unconnected-(U8-PG-Pad7)") (class "Default")
      (node (ref "U8") (pin "7") (pinfunction "PG_7") (pintype "open_collector+no_connect"))
    )
    (net (code "29") (name "unconnected-(U9-PG-Pad7)") (class "Default")
      (node (ref "U9") (pin "7") (pinfunction "PG_7") (pintype "open_collector+no_connect"))
    )
    (net (code "30") (name "unconnected-(U10-PG-Pad7)") (class "Default")
      (node (ref "U10") (pin "7") (pinfunction "PG_7") (pintype "open_collector+no_connect"))
    )
    (net (code "31") (name "unconnected-(U11-PG-Pad7)") (class "Default")
      (node (ref "U11") (pin "7") (pinfunction "PG_7") (pintype "open_collector+no_connect"))
    )
  )
)
